# GR_actions.net
KiCad netlist of a schematic drawn in Altium Designer
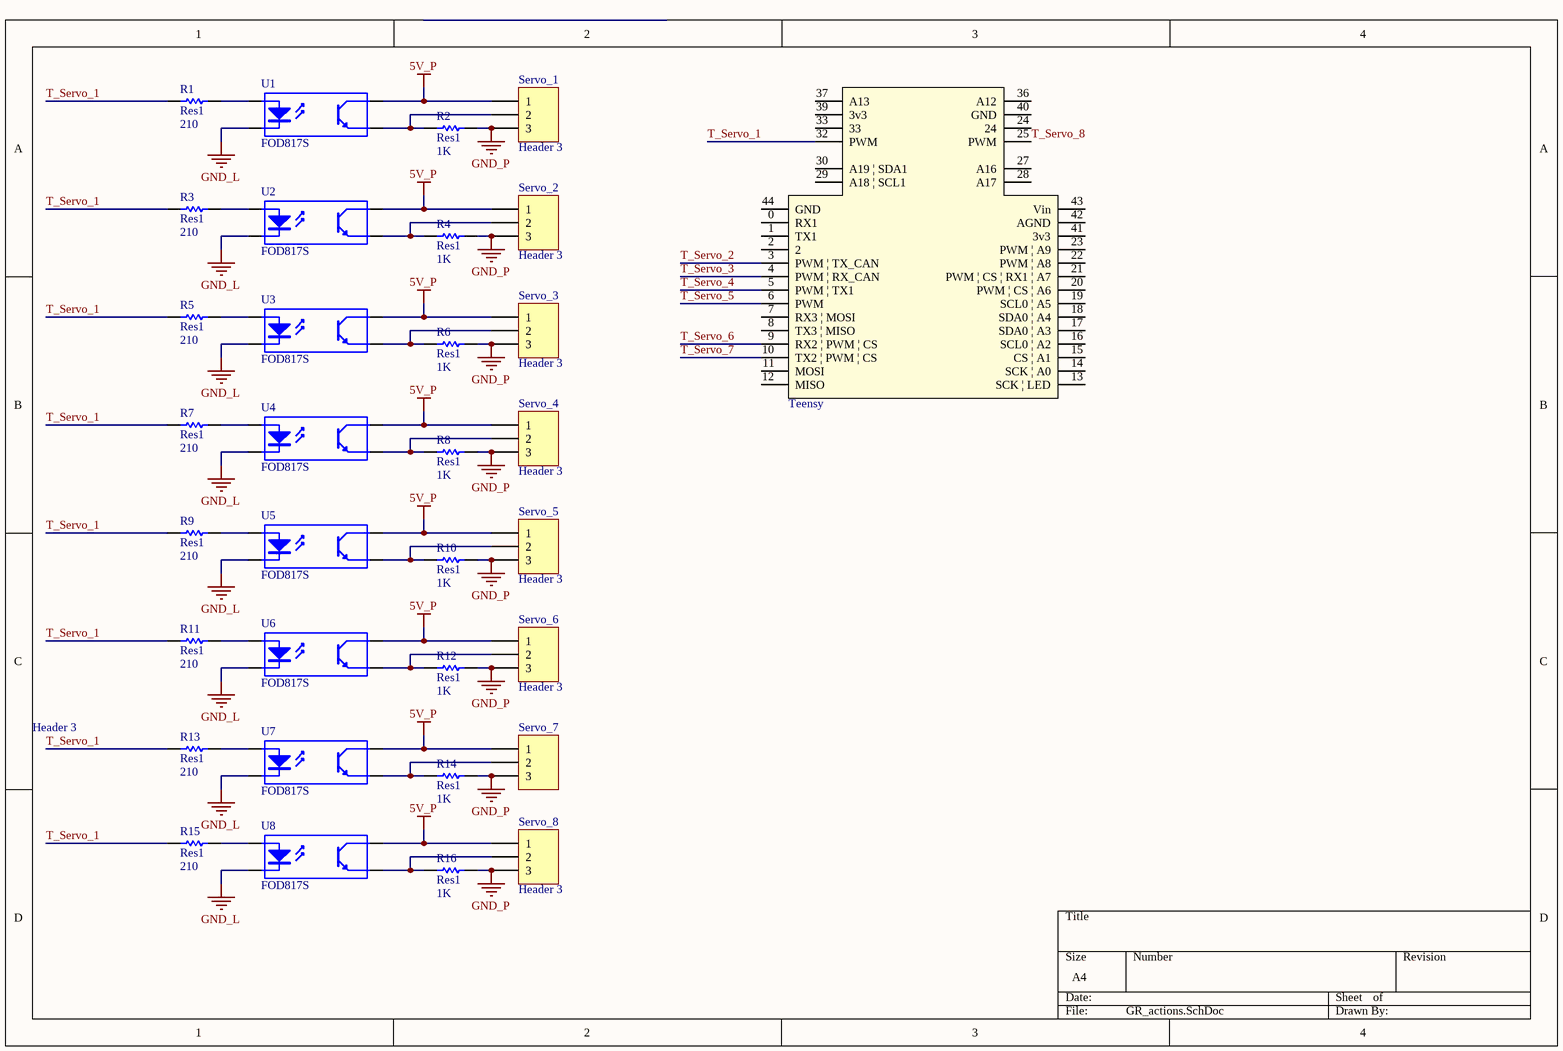
[diagram p0: GR_actions.SchDoc]

(export (version "E")
  (design (tool "Eeschema 10.0.6"))
  (components
    (comp (ref "R1")
      (value "Res1")
      (footprint "Resistor 1206")
      (description "Resistor")
      (fields (field (name "ALTIUM_VALUE") "210") (field (name "PUBLISHER") "Altium Limited"))
      (libsource (lib "Miscellaneous Devices") (part "Res1"))
    )
    (comp (ref "R2")
      (value "Res1")
      (footprint "Resistor 1206")
      (description "Resistor")
      (fields (field (name "ALTIUM_VALUE") "1K") (field (name "PUBLISHER") "Altium Limited"))
      (libsource (lib "Miscellaneous Devices") (part "Res1"))
    )
    (comp (ref "R3")
      (value "Res1")
      (footprint "Resistor 1206")
      (description "Resistor")
      (fields (field (name "ALTIUM_VALUE") "210") (field (name "PUBLISHER") "Altium Limited"))
      (libsource (lib "Miscellaneous Devices") (part "Res1"))
    )
    (comp (ref "R4")
      (value "Res1")
      (footprint "Resistor 1206")
      (description "Resistor")
      (fields (field (name "ALTIUM_VALUE") "1K") (field (name "PUBLISHER") "Altium Limited"))
      (libsource (lib "Miscellaneous Devices") (part "Res1"))
    )
    (comp (ref "R5")
      (value "Res1")
      (footprint "Resistor 1206")
      (description "Resistor")
      (fields (field (name "ALTIUM_VALUE") "210") (field (name "PUBLISHER") "Altium Limited"))
      (libsource (lib "Miscellaneous Devices") (part "Res1"))
    )
    (comp (ref "R6")
      (value "Res1")
      (footprint "Resistor 1206")
      (description "Resistor")
      (fields (field (name "ALTIUM_VALUE") "1K") (field (name "PUBLISHER") "Altium Limited"))
      (libsource (lib "Miscellaneous Devices") (part "Res1"))
    )
    (comp (ref "R7")
      (value "Res1")
      (footprint "Resistor 1206")
      (description "Resistor")
      (fields (field (name "ALTIUM_VALUE") "210") (field (name "PUBLISHER") "Altium Limited"))
      (libsource (lib "Miscellaneous Devices") (part "Res1"))
    )
    (comp (ref "R8")
      (value "Res1")
      (footprint "Resistor 1206")
      (description "Resistor")
      (fields (field (name "ALTIUM_VALUE") "1K") (field (name "PUBLISHER") "Altium Limited"))
      (libsource (lib "Miscellaneous Devices") (part "Res1"))
    )
    (comp (ref "R9")
      (value "Res1")
      (footprint "Resistor 1206")
      (description "Resistor")
      (fields (field (name "ALTIUM_VALUE") "210") (field (name "PUBLISHER") "Altium Limited"))
      (libsource (lib "Miscellaneous Devices") (part "Res1"))
    )
    (comp (ref "R10")
      (value "Res1")
      (footprint "Resistor 1206")
      (description "Resistor")
      (fields (field (name "ALTIUM_VALUE") "1K") (field (name "PUBLISHER") "Altium Limited"))
      (libsource (lib "Miscellaneous Devices") (part "Res1"))
    )
    (comp (ref "R11")
      (value "Res1")
      (footprint "Resistor 1206")
      (description "Resistor")
      (fields (field (name "ALTIUM_VALUE") "210") (field (name "PUBLISHER") "Altium Limited"))
      (libsource (lib "Miscellaneous Devices") (part "Res1"))
    )
    (comp (ref "R12")
      (value "Res1")
      (footprint "Resistor 1206")
      (description "Resistor")
      (fields (field (name "ALTIUM_VALUE") "1K") (field (name "PUBLISHER") "Altium Limited"))
      (libsource (lib "Miscellaneous Devices") (part "Res1"))
    )
    (comp (ref "R13")
      (value "Res1")
      (footprint "Resistor 1206")
      (description "Resistor")
      (fields (field (name "ALTIUM_VALUE") "210") (field (name "PUBLISHER") "Altium Limited"))
      (libsource (lib "Miscellaneous Devices") (part "Res1"))
    )
    (comp (ref "R14")
      (value "Res1")
      (footprint "Resistor 1206")
      (description "Resistor")
      (fields (field (name "ALTIUM_VALUE") "1K") (field (name "PUBLISHER") "Altium Limited"))
      (libsource (lib "Miscellaneous Devices") (part "Res1"))
    )
    (comp (ref "R15")
      (value "Res1")
      (footprint "Resistor 1206")
      (description "Resistor")
      (fields (field (name "ALTIUM_VALUE") "210") (field (name "PUBLISHER") "Altium Limited"))
      (libsource (lib "Miscellaneous Devices") (part "Res1"))
    )
    (comp (ref "R16")
      (value "Res1")
      (footprint "Resistor 1206")
      (description "Resistor")
      (fields (field (name "ALTIUM_VALUE") "1K") (field (name "PUBLISHER") "Altium Limited"))
      (libsource (lib "Miscellaneous Devices") (part "Res1"))
    )
    (comp (ref "Servo_1")
      (value "Header 3")
      (footprint "S3B-XH-A")
      (description "Header, 3-Pin")
      (fields (field (name "PUBLISHER") "Altium Limited"))
      (libsource (lib "Miscellaneous Connectors") (part "Header 3"))
    )
    (comp (ref "Servo_2")
      (value "Header 3")
      (footprint "S3B-XH-A")
      (description "Header, 3-Pin")
      (fields (field (name "PUBLISHER") "Altium Limited"))
      (libsource (lib "Miscellaneous Connectors") (part "Header 3"))
    )
    (comp (ref "Servo_3")
      (value "Header 3")
      (footprint "S3B-XH-A")
      (description "Header, 3-Pin")
      (fields (field (name "PUBLISHER") "Altium Limited"))
      (libsource (lib "Miscellaneous Connectors") (part "Header 3"))
    )
    (comp (ref "Servo_4")
      (value "Header 3")
      (footprint "S3B-XH-A")
      (description "Header, 3-Pin")
      (fields (field (name "PUBLISHER") "Altium Limited"))
      (libsource (lib "Miscellaneous Connectors") (part "Header 3"))
    )
    (comp (ref "Servo_5")
      (value "Header 3")
      (footprint "S3B-XH-A")
      (description "Header, 3-Pin")
      (fields (field (name "PUBLISHER") "Altium Limited"))
      (libsource (lib "Miscellaneous Connectors") (part "Header 3"))
    )
    (comp (ref "Servo_6")
      (value "Header 3")
      (footprint "S3B-XH-A")
      (description "Header, 3-Pin")
      (fields (field (name "PUBLISHER") "Altium Limited"))
      (libsource (lib "Miscellaneous Connectors") (part "Header 3"))
    )
    (comp (ref "Servo_7")
      (value "Header 3")
      (footprint "S3B-XH-A")
      (description "Header, 3-Pin")
      (fields (field (name "PUBLISHER") "Altium Limited"))
      (libsource (lib "Miscellaneous Connectors") (part "Header 3"))
    )
    (comp (ref "Servo_8")
      (value "Header 3")
      (footprint "S3B-XH-A")
      (description "Header, 3-Pin")
      (fields (field (name "PUBLISHER") "Altium Limited"))
      (libsource (lib "Miscellaneous Connectors") (part "Header 3"))
    )
    (comp (ref "Teensy")
      (value "Teensy 3.2")
      (footprint "Robot_2020:teensy_3,2_Base_Roulante")
      (libsource (lib "Robot_2020") (part "teensy3.2_Base_Roulante"))
    )
    (comp (ref "U1")
      (value "FOD817S")
      (footprint "SOP254P1016X385-4N")
      (description "4-Pin Phototransistor Optocoupler")
      (fields (field (name "PUBLISHER") "Altium Limited"))
      (libsource (lib "Miscellaneous Devices") (part "Optoisolator1"))
    )
    (comp (ref "U2")
      (value "FOD817S")
      (footprint "SOP254P1016X385-4N")
      (description "4-Pin Phototransistor Optocoupler")
      (fields (field (name "PUBLISHER") "Altium Limited"))
      (libsource (lib "Miscellaneous Devices") (part "Optoisolator1"))
    )
    (comp (ref "U3")
      (value "FOD817S")
      (footprint "SOP254P1016X385-4N")
      (description "4-Pin Phototransistor Optocoupler")
      (fields (field (name "PUBLISHER") "Altium Limited"))
      (libsource (lib "Miscellaneous Devices") (part "Optoisolator1"))
    )
    (comp (ref "U4")
      (value "FOD817S")
      (footprint "SOP254P1016X385-4N")
      (description "4-Pin Phototransistor Optocoupler")
      (fields (field (name "PUBLISHER") "Altium Limited"))
      (libsource (lib "Miscellaneous Devices") (part "Optoisolator1"))
    )
    (comp (ref "U5")
      (value "FOD817S")
      (footprint "SOP254P1016X385-4N")
      (description "4-Pin Phototransistor Optocoupler")
      (fields (field (name "PUBLISHER") "Altium Limited"))
      (libsource (lib "Miscellaneous Devices") (part "Optoisolator1"))
    )
    (comp (ref "U6")
      (value "FOD817S")
      (footprint "SOP254P1016X385-4N")
      (description "4-Pin Phototransistor Optocoupler")
      (fields (field (name "PUBLISHER") "Altium Limited"))
      (libsource (lib "Miscellaneous Devices") (part "Optoisolator1"))
    )
    (comp (ref "U7")
      (value "FOD817S")
      (footprint "SOP254P1016X385-4N")
      (description "4-Pin Phototransistor Optocoupler")
      (fields (field (name "PUBLISHER") "Altium Limited"))
      (libsource (lib "Miscellaneous Devices") (part "Optoisolator1"))
    )
    (comp (ref "U8")
      (value "FOD817S")
      (footprint "SOP254P1016X385-4N")
      (description "4-Pin Phototransistor Optocoupler")
      (fields (field (name "PUBLISHER") "Altium Limited"))
      (libsource (lib "Miscellaneous Devices") (part "Optoisolator1"))
    )
  )
  (nets
    (net (code "1") (name "/T_Servo_1") (class "Default")
      (node (ref "R1") (pin "2") (pinfunction "2_2") (pintype "passive"))
      (node (ref "R11") (pin "2") (pinfunction "2_2") (pintype "passive"))
      (node (ref "R13") (pin "2") (pinfunction "2_2") (pintype "passive"))
      (node (ref "R15") (pin "2") (pinfunction "2_2") (pintype "passive"))
      (node (ref "R3") (pin "2") (pinfunction "2_2") (pintype "passive"))
      (node (ref "R5") (pin "2") (pinfunction "2_2") (pintype "passive"))
      (node (ref "R7") (pin "2") (pinfunction "2_2") (pintype "passive"))
      (node (ref "R9") (pin "2") (pinfunction "2_2") (pintype "passive"))
      (node (ref "Teensy") (pin "32") (pinfunction "PWM_32") (pintype "passive"))
    )
    (net (code "2") (name "/T_Servo_2") (class "Default")
      (node (ref "Teensy") (pin "3") (pinfunction "PWM_¦_TX_CAN_3") (pintype "passive"))
    )
    (net (code "3") (name "/T_Servo_3") (class "Default")
      (node (ref "Teensy") (pin "4") (pinfunction "PWM_¦_RX_CAN_4") (pintype "passive"))
    )
    (net (code "4") (name "/T_Servo_4") (class "Default")
      (node (ref "Teensy") (pin "5") (pinfunction "PWM_¦_TX1_5") (pintype "passive"))
    )
    (net (code "5") (name "/T_Servo_5") (class "Default")
      (node (ref "Teensy") (pin "6") (pinfunction "PWM_6") (pintype "passive"))
    )
    (net (code "6") (name "/T_Servo_6") (class "Default")
      (node (ref "Teensy") (pin "9") (pinfunction "RX2_¦_PWM_¦_CS_9") (pintype "passive"))
    )
    (net (code "7") (name "/T_Servo_7") (class "Default")
      (node (ref "Teensy") (pin "10") (pinfunction "TX2_¦_PWM_¦_CS_10") (pintype "passive"))
    )
    (net (code "8") (name "/T_Servo_8") (class "Default")
      (node (ref "Teensy") (pin "25") (pinfunction "PWM_25") (pintype "passive"))
    )
    (net (code "9") (name "5V_P") (class "Default")
      (node (ref "Servo_1") (pin "1") (pinfunction "1_1") (pintype "passive"))
      (node (ref "Servo_2") (pin "1") (pinfunction "1_1") (pintype "passive"))
      (node (ref "Servo_3") (pin "1") (pinfunction "1_1") (pintype "passive"))
      (node (ref "Servo_4") (pin "1") (pinfunction "1_1") (pintype "passive"))
      (node (ref "Servo_5") (pin "1") (pinfunction "1_1") (pintype "passive"))
      (node (ref "Servo_6") (pin "1") (pinfunction "1_1") (pintype "passive"))
      (node (ref "Servo_7") (pin "1") (pinfunction "1_1") (pintype "passive"))
      (node (ref "Servo_8") (pin "1") (pinfunction "1_1") (pintype "passive"))
      (node (ref "U1") (pin "4") (pinfunction "C_4") (pintype "passive"))
      (node (ref "U2") (pin "4") (pinfunction "C_4") (pintype "passive"))
      (node (ref "U3") (pin "4") (pinfunction "C_4") (pintype "passive"))
      (node (ref "U4") (pin "4") (pinfunction "C_4") (pintype "passive"))
      (node (ref "U5") (pin "4") (pinfunction "C_4") (pintype "passive"))
      (node (ref "U6") (pin "4") (pinfunction "C_4") (pintype "passive"))
      (node (ref "U7") (pin "4") (pinfunction "C_4") (pintype "passive"))
      (node (ref "U8") (pin "4") (pinfunction "C_4") (pintype "passive"))
    )
    (net (code "10") (name "GND_L") (class "Default")
      (node (ref "U1") (pin "2") (pinfunction "K_2") (pintype "passive"))
      (node (ref "U2") (pin "2") (pinfunction "K_2") (pintype "passive"))
      (node (ref "U3") (pin "2") (pinfunction "K_2") (pintype "passive"))
      (node (ref "U4") (pin "2") (pinfunction "K_2") (pintype "passive"))
      (node (ref "U5") (pin "2") (pinfunction "K_2") (pintype "passive"))
      (node (ref "U6") (pin "2") (pinfunction "K_2") (pintype "passive"))
      (node (ref "U7") (pin "2") (pinfunction "K_2") (pintype "passive"))
      (node (ref "U8") (pin "2") (pinfunction "K_2") (pintype "passive"))
    )
    (net (code "11") (name "GND_P") (class "Default")
      (node (ref "R10") (pin "1") (pinfunction "1_1") (pintype "passive"))
      (node (ref "R12") (pin "1") (pinfunction "1_1") (pintype "passive"))
      (node (ref "R14") (pin "1") (pinfunction "1_1") (pintype "passive"))
      (node (ref "R16") (pin "1") (pinfunction "1_1") (pintype "passive"))
      (node (ref "R2") (pin "1") (pinfunction "1_1") (pintype "passive"))
      (node (ref "R4") (pin "1") (pinfunction "1_1") (pintype "passive"))
      (node (ref "R6") (pin "1") (pinfunction "1_1") (pintype "passive"))
      (node (ref "R8") (pin "1") (pinfunction "1_1") (pintype "passive"))
      (node (ref "Servo_1") (pin "3") (pinfunction "3_3") (pintype "passive"))
      (node (ref "Servo_2") (pin "3") (pinfunction "3_3") (pintype "passive"))
      (node (ref "Servo_3") (pin "3") (pinfunction "3_3") (pintype "passive"))
      (node (ref "Servo_4") (pin "3") (pinfunction "3_3") (pintype "passive"))
      (node (ref "Servo_5") (pin "3") (pinfunction "3_3") (pintype "passive"))
      (node (ref "Servo_6") (pin "3") (pinfunction "3_3") (pintype "passive"))
      (node (ref "Servo_7") (pin "3") (pinfunction "3_3") (pintype "passive"))
      (node (ref "Servo_8") (pin "3") (pinfunction "3_3") (pintype "passive"))
    )
    (net (code "12") (name "Net-(U1-A)") (class "Default")
      (node (ref "R1") (pin "1") (pinfunction "1_1") (pintype "passive"))
      (node (ref "U1") (pin "1") (pinfunction "A_1") (pintype "passive"))
    )
    (net (code "13") (name "Net-(U1-E)") (class "Default")
      (node (ref "R2") (pin "2") (pinfunction "2_2") (pintype "passive"))
      (node (ref "Servo_1") (pin "2") (pinfunction "2_2") (pintype "passive"))
      (node (ref "U1") (pin "3") (pinfunction "E_3") (pintype "passive"))
    )
    (net (code "14") (name "Net-(U2-A)") (class "Default")
      (node (ref "R3") (pin "1") (pinfunction "1_1") (pintype "passive"))
      (node (ref "U2") (pin "1") (pinfunction "A_1") (pintype "passive"))
    )
    (net (code "15") (name "Net-(U2-E)") (class "Default")
      (node (ref "R4") (pin "2") (pinfunction "2_2") (pintype "passive"))
      (node (ref "Servo_2") (pin "2") (pinfunction "2_2") (pintype "passive"))
      (node (ref "U2") (pin "3") (pinfunction "E_3") (pintype "passive"))
    )
    (net (code "16") (name "Net-(U3-A)") (class "Default")
      (node (ref "R5") (pin "1") (pinfunction "1_1") (pintype "passive"))
      (node (ref "U3") (pin "1") (pinfunction "A_1") (pintype "passive"))
    )
    (net (code "17") (name "Net-(U3-E)") (class "Default")
      (node (ref "R6") (pin "2") (pinfunction "2_2") (pintype "passive"))
      (node (ref "Servo_3") (pin "2") (pinfunction "2_2") (pintype "passive"))
      (node (ref "U3") (pin "3") (pinfunction "E_3") (pintype "passive"))
    )
    (net (code "18") (name "Net-(U4-A)") (class "Default")
      (node (ref "R7") (pin "1") (pinfunction "1_1") (pintype "passive"))
      (node (ref "U4") (pin "1") (pinfunction "A_1") (pintype "passive"))
    )
    (net (code "19") (name "Net-(U4-E)") (class "Default")
      (node (ref "R8") (pin "2") (pinfunction "2_2") (pintype "passive"))
      (node (ref "Servo_4") (pin "2") (pinfunction "2_2") (pintype "passive"))
      (node (ref "U4") (pin "3") (pinfunction "E_3") (pintype "passive"))
    )
    (net (code "20") (name "Net-(U5-A)") (class "Default")
      (node (ref "R9") (pin "1") (pinfunction "1_1") (pintype "passive"))
      (node (ref "U5") (pin "1") (pinfunction "A_1") (pintype "passive"))
    )
    (net (code "21") (name "Net-(U5-E)") (class "Default")
      (node (ref "R10") (pin "2") (pinfunction "2_2") (pintype "passive"))
      (node (ref "Servo_5") (pin "2") (pinfunction "2_2") (pintype "passive"))
      (node (ref "U5") (pin "3") (pinfunction "E_3") (pintype "passive"))
    )
    (net (code "22") (name "Net-(U6-A)") (class "Default")
      (node (ref "R11") (pin "1") (pinfunction "1_1") (pintype "passive"))
      (node (ref "U6") (pin "1") (pinfunction "A_1") (pintype "passive"))
    )
    (net (code "23") (name "Net-(U6-E)") (class "Default")
      (node (ref "R12") (pin "2") (pinfunction "2_2") (pintype "passive"))
      (node (ref "Servo_6") (pin "2") (pinfunction "2_2") (pintype "passive"))
      (node (ref "U6") (pin "3") (pinfunction "E_3") (pintype "passive"))
    )
    (net (code "24") (name "Net-(U7-A)") (class "Default")
      (node (ref "R13") (pin "1") (pinfunction "1_1") (pintype "passive"))
      (node (ref "U7") (pin "1") (pinfunction "A_1") (pintype "passive"))
    )
    (net (code "25") (name "Net-(U7-E)") (class "Default")
      (node (ref "R14") (pin "2") (pinfunction "2_2") (pintype "passive"))
      (node (ref "Servo_7") (pin "2") (pinfunction "2_2") (pintype "passive"))
      (node (ref "U7") (pin "3") (pinfunction "E_3") (pintype "passive"))
    )
    (net (code "26") (name "Net-(U8-A)") (class "Default")
      (node (ref "R15") (pin "1") (pinfunction "1_1") (pintype "passive"))
      (node (ref "U8") (pin "1") (pinfunction "A_1") (pintype "passive"))
    )
    (net (code "27") (name "Net-(U8-E)") (class "Default")
      (node (ref "R16") (pin "2") (pinfunction "2_2") (pintype "passive"))
      (node (ref "Servo_8") (pin "2") (pinfunction "2_2") (pintype "passive"))
      (node (ref "U8") (pin "3") (pinfunction "E_3") (pintype "passive"))
    )
    (net (code "28") (name "unconnected-(Teensy-3v3-Pad39)") (class "Default")
      (node (ref "Teensy") (pin "39") (pinfunction "3v3_39") (pintype "passive"))
    )
    (net (code "29") (name "unconnected-(Teensy-3v3-Pad41)") (class "Default")
      (node (ref "Teensy") (pin "41") (pinfunction "3v3_41") (pintype "passive"))
    )
    (net (code "30") (name "unconnected-(Teensy-A12-Pad36)") (class "Default")
      (node (ref "Teensy") (pin "36") (pinfunction "A12_36") (pintype "passive"))
    )
    (net (code "31") (name "unconnected-(Teensy-A13-Pad37)") (class "Default")
      (node (ref "Teensy") (pin "37") (pinfunction "A13_37") (pintype "passive"))
    )
    (net (code "32") (name "unconnected-(Teensy-A16-Pad27)") (class "Default")
      (node (ref "Teensy") (pin "27") (pinfunction "A16_27") (pintype "passive"))
    )
    (net (code "33") (name "unconnected-(Teensy-A17-Pad28)") (class "Default")
      (node (ref "Teensy") (pin "28") (pinfunction "A17_28") (pintype "passive"))
    )
    (net (code "34") (name "unconnected-(Teensy-A18_¦_SCL1-Pad29)") (class "Default")
      (node (ref "Teensy") (pin "29") (pinfunction "A18_¦_SCL1_29") (pintype "passive"))
    )
    (net (code "35") (name "unconnected-(Teensy-A19_¦_SDA1-Pad30)") (class "Default")
      (node (ref "Teensy") (pin "30") (pinfunction "A19_¦_SDA1_30") (pintype "passive"))
    )
    (net (code "36") (name "unconnected-(Teensy-AGND-Pad42)") (class "Default")
      (node (ref "Teensy") (pin "42") (pinfunction "AGND_42") (pintype "passive"))
    )
    (net (code "37") (name "unconnected-(Teensy-CS_¦_A1-Pad15)") (class "Default")
      (node (ref "Teensy") (pin "15") (pinfunction "CS_¦_A1_15") (pintype "passive"))
    )
    (net (code "38") (name "unconnected-(Teensy-GND-Pad40)") (class "Default")
      (node (ref "Teensy") (pin "40") (pinfunction "GND_40") (pintype "passive"))
    )
    (net (code "39") (name "unconnected-(Teensy-GND-Pad44)") (class "Default")
      (node (ref "Teensy") (pin "44") (pinfunction "GND_44") (pintype "passive"))
    )
    (net (code "40") (name "unconnected-(Teensy-MISO-Pad12)") (class "Default")
      (node (ref "Teensy") (pin "12") (pinfunction "MISO_12") (pintype "passive"))
    )
    (net (code "41") (name "unconnected-(Teensy-MOSI-Pad11)") (class "Default")
      (node (ref "Teensy") (pin "11") (pinfunction "MOSI_11") (pintype "passive"))
    )
    (net (code "42") (name "unconnected-(Teensy-PWM_¦_A8-Pad22)") (class "Default")
      (node (ref "Teensy") (pin "22") (pinfunction "PWM_¦_A8_22") (pintype "passive"))
    )
    (net (code "43") (name "unconnected-(Teensy-PWM_¦_A9-Pad23)") (class "Default")
      (node (ref "Teensy") (pin "23") (pinfunction "PWM_¦_A9_23") (pintype "passive"))
    )
    (net (code "44") (name "unconnected-(Teensy-PWM_¦_CS_¦_A6-Pad20)") (class "Default")
      (node (ref "Teensy") (pin "20") (pinfunction "PWM_¦_CS_¦_A6_20") (pintype "passive"))
    )
    (net (code "45") (name "unconnected-(Teensy-PWM_¦_CS_¦_RX1_¦_A7-Pad21)") (class "Default")
      (node (ref "Teensy") (pin "21") (pinfunction "PWM_¦_CS_¦_RX1_¦_A7_21") (pintype "passive"))
    )
    (net (code "46") (name "unconnected-(Teensy-Pad2)") (class "Default")
      (node (ref "Teensy") (pin "2") (pinfunction "2_2") (pintype "passive"))
    )
    (net (code "47") (name "unconnected-(Teensy-Pad24)") (class "Default")
      (node (ref "Teensy") (pin "24") (pinfunction "24_24") (pintype "passive"))
    )
    (net (code "48") (name "unconnected-(Teensy-Pad33)") (class "Default")
      (node (ref "Teensy") (pin "33") (pinfunction "33_33") (pintype "passive"))
    )
    (net (code "49") (name "unconnected-(Teensy-RX1-Pad0)") (class "Default")
      (node (ref "Teensy") (pin "0") (pinfunction "RX1_0") (pintype "passive"))
    )
    (net (code "50") (name "unconnected-(Teensy-RX3_¦_MOSI-Pad7)") (class "Default")
      (node (ref "Teensy") (pin "7") (pinfunction "RX3_¦_MOSI_7") (pintype "passive"))
    )
    (net (code "51") (name "unconnected-(Teensy-SCK_¦_A0-Pad14)") (class "Default")
      (node (ref "Teensy") (pin "14") (pinfunction "SCK_¦_A0_14") (pintype "passive"))
    )
    (net (code "52") (name "unconnected-(Teensy-SCK_¦_LED-Pad13)") (class "Default")
      (node (ref "Teensy") (pin "13") (pinfunction "SCK_¦_LED_13") (pintype "passive"))
    )
    (net (code "53") (name "unconnected-(Teensy-SCL0_¦_A2-Pad16)") (class "Default")
      (node (ref "Teensy") (pin "16") (pinfunction "SCL0_¦_A2_16") (pintype "passive"))
    )
    (net (code "54") (name "unconnected-(Teensy-SCL0_¦_A5-Pad19)") (class "Default")
      (node (ref "Teensy") (pin "19") (pinfunction "SCL0_¦_A5_19") (pintype "passive"))
    )
    (net (code "55") (name "unconnected-(Teensy-SDA0_¦_A3-Pad17)") (class "Default")
      (node (ref "Teensy") (pin "17") (pinfunction "SDA0_¦_A3_17") (pintype "passive"))
    )
    (net (code "56") (name "unconnected-(Teensy-SDA0_¦_A4-Pad18)") (class "Default")
      (node (ref "Teensy") (pin "18") (pinfunction "SDA0_¦_A4_18") (pintype "passive"))
    )
    (net (code "57") (name "unconnected-(Teensy-TX1-Pad1)") (class "Default")
      (node (ref "Teensy") (pin "1") (pinfunction "TX1_1") (pintype "passive"))
    )
    (net (code "58") (name "unconnected-(Teensy-TX3_¦_MISO-Pad8)") (class "Default")
      (node (ref "Teensy") (pin "8") (pinfunction "TX3_¦_MISO_8") (pintype "passive"))
    )
    (net (code "59") (name "unconnected-(Teensy-Vin-Pad43)") (class "Default")
      (node (ref "Teensy") (pin "43") (pinfunction "Vin_43") (pintype "passive"))
    )
  )
)
